# rocketradio.net
KiCad netlist of a schematic drawn in EAGLE
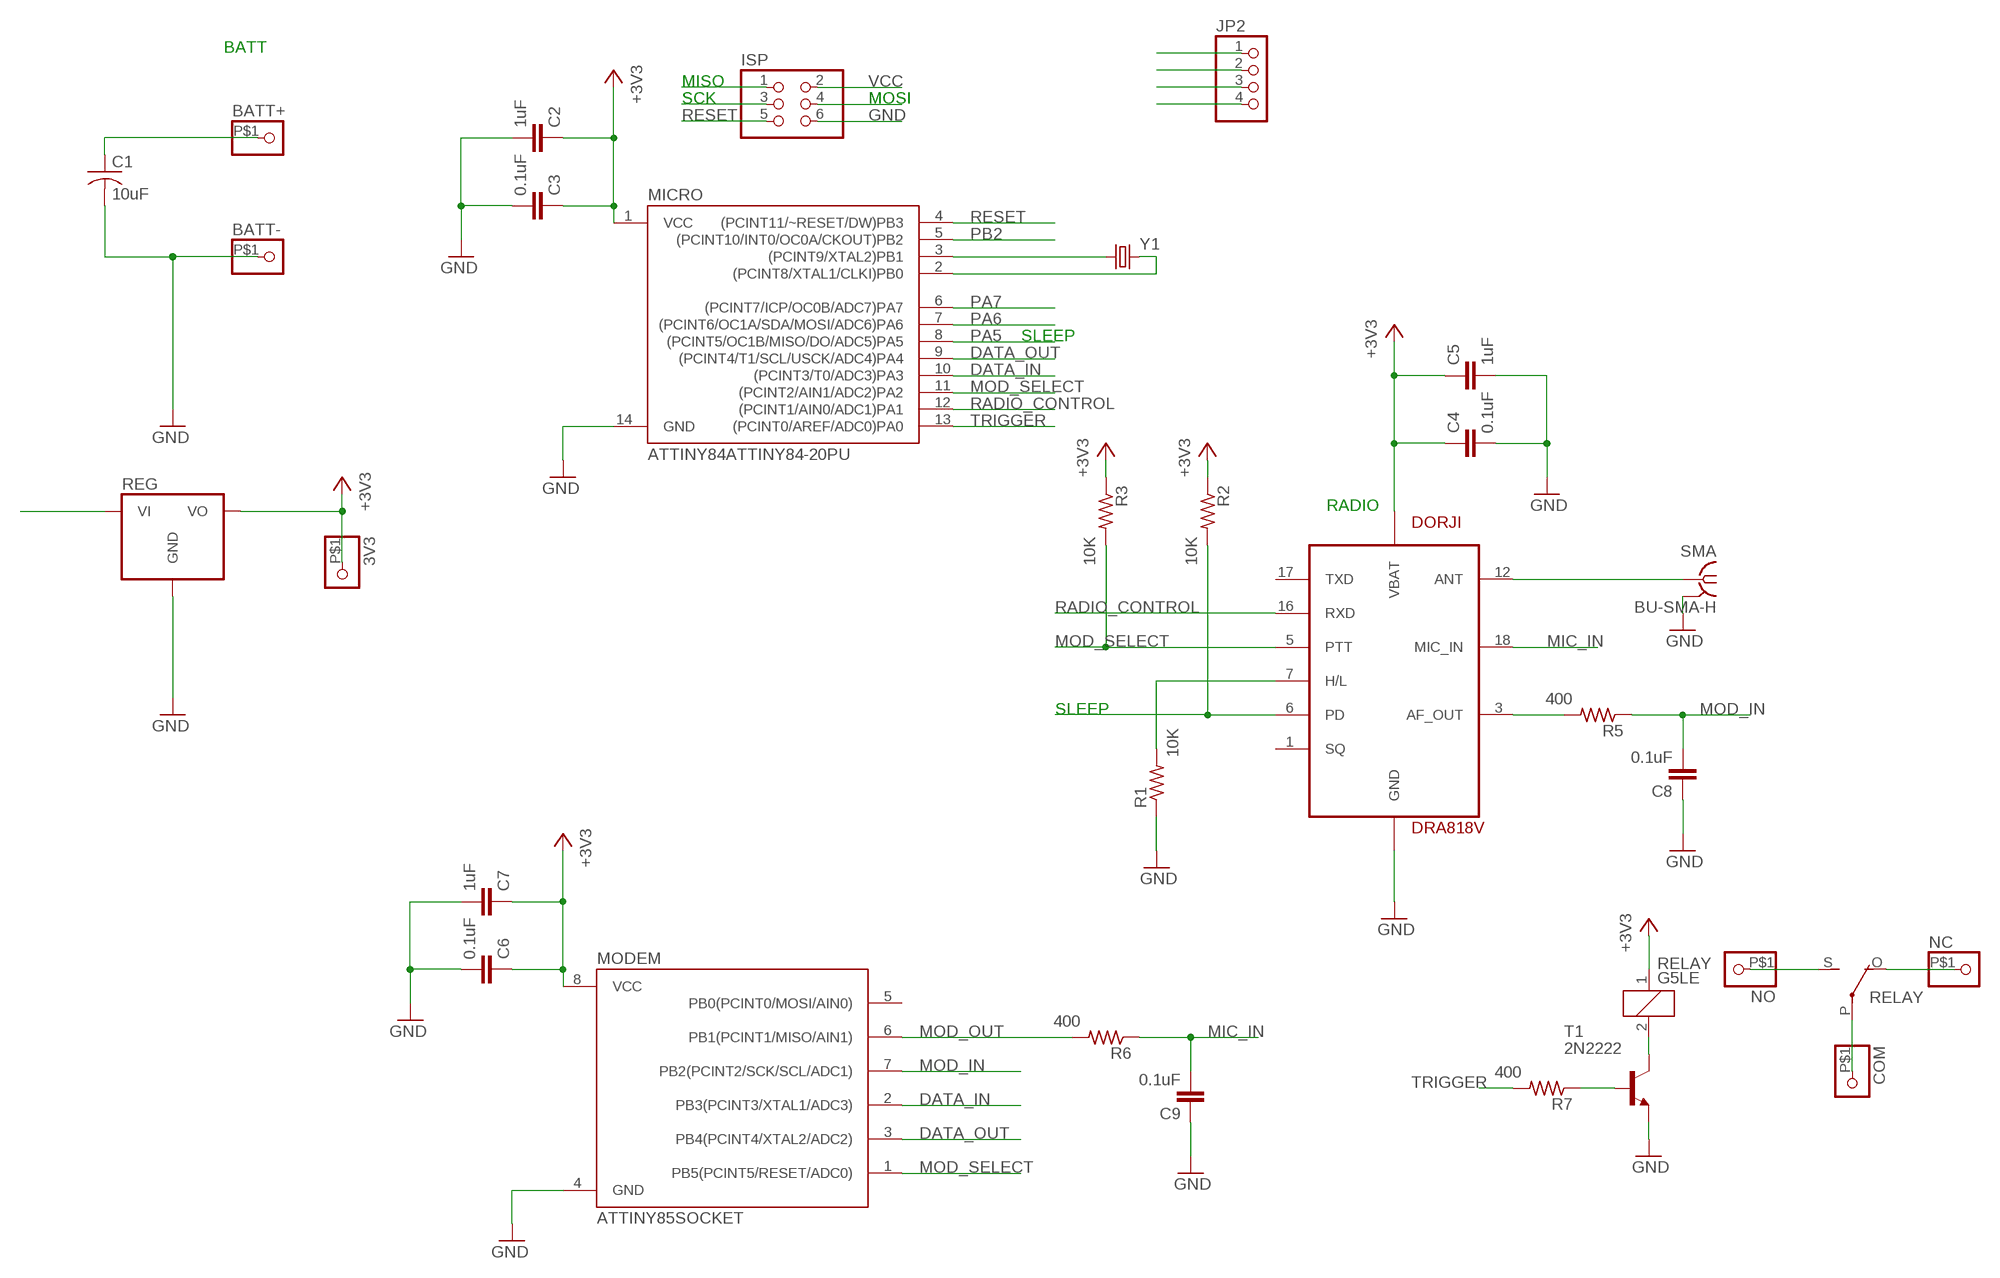
[diagram p0: schematic, sheet 1]

(export (version "E")
  (design (tool "Eeschema 10.0.6"))
  (components
    (comp (ref "3V3")
      (value "PINHD-1X1")
      (footprint "eagle-import:1X01")
      (libsource (lib "eagle-import") (part "PINHD-1X1"))
    )
    (comp (ref "BATT+")
      (value "PINHD-1X1")
      (footprint "eagle-import:1X01")
      (libsource (lib "eagle-import") (part "PINHD-1X1"))
    )
    (comp (ref "BATT-")
      (value "PINHD-1X1")
      (footprint "eagle-import:1X01")
      (libsource (lib "eagle-import") (part "PINHD-1X1"))
    )
    (comp (ref "C1")
      (value "10uF")
      (footprint "eagle-import:C025-050X050")
      (libsource (lib "eagle-import") (part "C-US025-050X050"))
    )
    (comp (ref "C2")
      (value "1uF")
      (footprint "eagle-import:C0603")
      (libsource (lib "eagle-import") (part "C-EUC0603"))
    )
    (comp (ref "C3")
      (value "0.1uF")
      (footprint "eagle-import:C0603")
      (libsource (lib "eagle-import") (part "C-EUC0603"))
    )
    (comp (ref "C4")
      (value "0.1uF")
      (footprint "eagle-import:C0603")
      (libsource (lib "eagle-import") (part "C-EUC0603"))
    )
    (comp (ref "C5")
      (value "1uF")
      (footprint "eagle-import:C0603")
      (libsource (lib "eagle-import") (part "C-EUC0603"))
    )
    (comp (ref "C6")
      (value "0.1uF")
      (footprint "eagle-import:C0603")
      (libsource (lib "eagle-import") (part "C-EUC0603"))
    )
    (comp (ref "C7")
      (value "1uF")
      (footprint "eagle-import:C0603")
      (libsource (lib "eagle-import") (part "C-EUC0603"))
    )
    (comp (ref "C8")
      (value "0.1uF")
      (footprint "eagle-import:C0603")
      (libsource (lib "eagle-import") (part "C-EUC0603"))
    )
    (comp (ref "C9")
      (value "0.1uF")
      (footprint "eagle-import:C0603")
      (libsource (lib "eagle-import") (part "C-EUC0603"))
    )
    (comp (ref "COM")
      (value "PINHD-1X1")
      (footprint "eagle-import:1X01")
      (libsource (lib "eagle-import") (part "PINHD-1X1"))
    )
    (comp (ref "DORJI")
      (value "DRA818V")
      (footprint "eagle-import:DORJI")
      (libsource (lib "eagle-import") (part "DORJIDRA818V"))
    )
    (comp (ref "ISP")
      (value "PINHD-2X3")
      (footprint "eagle-import:2X03")
      (libsource (lib "eagle-import") (part "PINHD-2X3"))
    )
    (comp (ref "JP2")
      (value "PINHD-1X4")
      (footprint "eagle-import:1X04")
      (libsource (lib "eagle-import") (part "PINHD-1X4"))
    )
    (comp (ref "MICRO")
      (value "ATTINY84ATTINY84-20PU")
      (footprint "eagle-import:DIL14")
      (libsource (lib "eagle-import") (part "ATTINY84ATTINY84-20PU"))
    )
    (comp (ref "MODEM")
      (value "ATTINY85SOCKET")
      (footprint "eagle-import:SOCKET-08")
      (libsource (lib "eagle-import") (part "ATTINY85SOCKET"))
    )
    (comp (ref "NC")
      (value "PINHD-1X1")
      (footprint "eagle-import:1X01")
      (libsource (lib "eagle-import") (part "PINHD-1X1"))
    )
    (comp (ref "NO")
      (value "PINHD-1X1")
      (footprint "eagle-import:1X01")
      (libsource (lib "eagle-import") (part "PINHD-1X1"))
    )
    (comp (ref "R1")
      (value "10K")
      (footprint "eagle-import:R0603")
      (libsource (lib "eagle-import") (part "R-US_R0603"))
    )
    (comp (ref "R2")
      (value "10K")
      (footprint "eagle-import:R0603")
      (libsource (lib "eagle-import") (part "R-US_R0603"))
    )
    (comp (ref "R3")
      (value "10K")
      (footprint "eagle-import:R0603")
      (libsource (lib "eagle-import") (part "R-US_R0603"))
    )
    (comp (ref "R5")
      (value "400")
      (footprint "eagle-import:R0603")
      (libsource (lib "eagle-import") (part "R-US_R0603"))
    )
    (comp (ref "R6")
      (value "400")
      (footprint "eagle-import:R0603")
      (libsource (lib "eagle-import") (part "R-US_R0603"))
    )
    (comp (ref "R7")
      (value "400")
      (footprint "eagle-import:R0603")
      (libsource (lib "eagle-import") (part "R-US_R0603"))
    )
    (comp (ref "REG")
      (value "AP1117-3.3SOT223")
      (footprint "eagle-import:SOT223")
      (libsource (lib "eagle-import") (part "AP1117-3.3SOT223"))
    )
    (comp (ref "RELAY")
      (value "G5LE")
      (footprint "eagle-import:G5LE")
      (libsource (lib "eagle-import") (part "G5LE"))
    )
    (comp (ref "SMA")
      (value "BU-SMA-H")
      (footprint "eagle-import:BU-SMA-H")
      (libsource (lib "eagle-import") (part "BU-SMA-H"))
    )
    (comp (ref "T1")
      (value "2N2222")
      (footprint "eagle-import:TO18")
      (libsource (lib "eagle-import") (part "2N2222"))
    )
    (comp (ref "Y1")
      (value "CRYSTAL")
      (footprint "eagle-import:MYSMD2_RESONATOR")
      (libsource (lib "eagle-import") (part "CRYSTAL"))
    )
  )
  (nets
    (net (code "1") (name "+3V3") (class "Default")
      (node (ref "3V3") (pin "P$1") (pinfunction "1_P$1") (pintype "passive"))
      (node (ref "C2") (pin "1") (pinfunction "1_1") (pintype "passive"))
      (node (ref "C3") (pin "1") (pinfunction "1_1") (pintype "passive"))
      (node (ref "C4") (pin "1") (pinfunction "1_1") (pintype "passive"))
      (node (ref "C5") (pin "1") (pinfunction "1_1") (pintype "passive"))
      (node (ref "C6") (pin "1") (pinfunction "1_1") (pintype "passive"))
      (node (ref "C7") (pin "1") (pinfunction "1_1") (pintype "passive"))
      (node (ref "DORJI") (pin "8") (pinfunction "VBAT_8") (pintype "bidirectional"))
      (node (ref "MICRO") (pin "1") (pinfunction "VCC_1") (pintype "bidirectional"))
      (node (ref "MODEM") (pin "8") (pinfunction "VCC_8") (pintype "bidirectional"))
      (node (ref "R2") (pin "1") (pinfunction "1_1") (pintype "passive"))
      (node (ref "R3") (pin "1") (pinfunction "1_1") (pintype "passive"))
      (node (ref "REG") (pin "2") (pinfunction "VO_2") (pintype "passive"))
      (node (ref "REG") (pin "4") (pinfunction "VO_4") (pintype "passive"))
      (node (ref "RELAY") (pin "1") (pinfunction "1_1") (pintype "passive"))
    )
    (net (code "2") (name "/BATT") (class "Default")
      (node (ref "BATT+") (pin "P$1") (pinfunction "1_P$1") (pintype "passive"))
      (node (ref "C1") (pin "1") (pinfunction "1_1") (pintype "passive"))
      (node (ref "REG") (pin "3") (pinfunction "VI_3") (pintype "input"))
    )
    (net (code "3") (name "/DATA_IN") (class "Default")
      (node (ref "MICRO") (pin "10") (pinfunction "(PCINT3/T0/ADC3)PA3_10") (pintype "bidirectional"))
      (node (ref "MODEM") (pin "2") (pinfunction "PB3(PCINT3/XTAL1/ADC3)_2") (pintype "bidirectional"))
    )
    (net (code "4") (name "/DATA_OUT") (class "Default")
      (node (ref "ISP") (pin "3") (pinfunction "3_3") (pintype "passive"))
      (node (ref "MICRO") (pin "9") (pinfunction "(PCINT4/T1/SCL/USCK/ADC4)PA4_9") (pintype "bidirectional"))
      (node (ref "MODEM") (pin "3") (pinfunction "PB4(PCINT4/XTAL2/ADC2)_3") (pintype "bidirectional"))
    )
    (net (code "5") (name "/MIC_IN") (class "Default")
      (node (ref "C9") (pin "2") (pinfunction "2_2") (pintype "passive"))
      (node (ref "DORJI") (pin "18") (pinfunction "MIC_IN_18") (pintype "bidirectional"))
      (node (ref "R6") (pin "1") (pinfunction "1_1") (pintype "passive"))
    )
    (net (code "6") (name "/MOD_IN") (class "Default")
      (node (ref "C8") (pin "2") (pinfunction "2_2") (pintype "passive"))
      (node (ref "MODEM") (pin "7") (pinfunction "PB2(PCINT2/SCK/SCL/ADC1)_7") (pintype "bidirectional"))
      (node (ref "R5") (pin "1") (pinfunction "1_1") (pintype "passive"))
    )
    (net (code "7") (name "/MOD_OUT") (class "Default")
      (node (ref "MODEM") (pin "6") (pinfunction "PB1(PCINT1/MISO/AIN1)_6") (pintype "bidirectional"))
      (node (ref "R6") (pin "2") (pinfunction "2_2") (pintype "passive"))
    )
    (net (code "8") (name "/MOD_SELECT") (class "Default")
      (node (ref "DORJI") (pin "5") (pinfunction "PTT_5") (pintype "bidirectional"))
      (node (ref "MICRO") (pin "11") (pinfunction "(PCINT2/AIN1/ADC2)PA2_11") (pintype "bidirectional"))
      (node (ref "MODEM") (pin "1") (pinfunction "PB5(PCINT5/RESET/ADC0)_1") (pintype "bidirectional"))
      (node (ref "R3") (pin "2") (pinfunction "2_2") (pintype "passive"))
    )
    (net (code "9") (name "/PA5") (class "Default")
      (node (ref "DORJI") (pin "6") (pinfunction "PD_6") (pintype "bidirectional"))
      (node (ref "ISP") (pin "1") (pinfunction "1_1") (pintype "passive"))
      (node (ref "JP2") (pin "4") (pinfunction "4_4") (pintype "passive"))
      (node (ref "MICRO") (pin "8") (pinfunction "(PCINT5/OC1B/MISO/DO/ADC5)PA5_8") (pintype "bidirectional"))
      (node (ref "R2") (pin "2") (pinfunction "2_2") (pintype "passive"))
    )
    (net (code "10") (name "/PA6") (class "Default")
      (node (ref "ISP") (pin "4") (pinfunction "4_4") (pintype "passive"))
      (node (ref "JP2") (pin "3") (pinfunction "3_3") (pintype "passive"))
      (node (ref "MICRO") (pin "7") (pinfunction "(PCINT6/OC1A/SDA/MOSI/ADC6)PA6_7") (pintype "bidirectional"))
    )
    (net (code "11") (name "/PA7") (class "Default")
      (node (ref "JP2") (pin "2") (pinfunction "2_2") (pintype "passive"))
      (node (ref "MICRO") (pin "6") (pinfunction "(PCINT7/ICP/OC0B/ADC7)PA7_6") (pintype "bidirectional"))
    )
    (net (code "12") (name "/PB2") (class "Default")
      (node (ref "JP2") (pin "1") (pinfunction "1_1") (pintype "passive"))
      (node (ref "MICRO") (pin "5") (pinfunction "(PCINT10/INT0/OC0A/CKOUT)PB2_5") (pintype "bidirectional"))
    )
    (net (code "13") (name "/RADIO_CONTROL") (class "Default")
      (node (ref "DORJI") (pin "16") (pinfunction "RXD_16") (pintype "bidirectional"))
      (node (ref "MICRO") (pin "12") (pinfunction "(PCINT1/AIN0/ADC1)PA1_12") (pintype "bidirectional"))
    )
    (net (code "14") (name "/RESET") (class "Default")
      (node (ref "ISP") (pin "5") (pinfunction "5_5") (pintype "passive"))
      (node (ref "MICRO") (pin "4") (pinfunction "(PCINT11/~{RESET/DW})PB3_4") (pintype "bidirectional"))
    )
    (net (code "15") (name "/TRIGGER") (class "Default")
      (node (ref "MICRO") (pin "13") (pinfunction "(PCINT0/AREF/ADC0)PA0_13") (pintype "bidirectional"))
      (node (ref "R7") (pin "2") (pinfunction "2_2") (pintype "passive"))
    )
    (net (code "16") (name "/VCC") (class "Default")
      (node (ref "ISP") (pin "2") (pinfunction "2_2") (pintype "passive"))
    )
    (net (code "17") (name "GND") (class "Default")
      (node (ref "BATT-") (pin "P$1") (pinfunction "1_P$1") (pintype "passive"))
      (node (ref "C1") (pin "2") (pinfunction "2_2") (pintype "passive"))
      (node (ref "C2") (pin "2") (pinfunction "2_2") (pintype "passive"))
      (node (ref "C3") (pin "2") (pinfunction "2_2") (pintype "passive"))
      (node (ref "C4") (pin "2") (pinfunction "2_2") (pintype "passive"))
      (node (ref "C5") (pin "2") (pinfunction "2_2") (pintype "passive"))
      (node (ref "C6") (pin "2") (pinfunction "2_2") (pintype "passive"))
      (node (ref "C7") (pin "2") (pinfunction "2_2") (pintype "passive"))
      (node (ref "C8") (pin "1") (pinfunction "1_1") (pintype "passive"))
      (node (ref "C9") (pin "1") (pinfunction "1_1") (pintype "passive"))
      (node (ref "DORJI") (pin "10") (pinfunction "GND_10") (pintype "bidirectional"))
      (node (ref "DORJI") (pin "9") (pinfunction "GND_9") (pintype "bidirectional"))
      (node (ref "ISP") (pin "6") (pinfunction "6_6") (pintype "passive"))
      (node (ref "MICRO") (pin "14") (pinfunction "GND_14") (pintype "bidirectional"))
      (node (ref "MODEM") (pin "4") (pinfunction "GND_4") (pintype "bidirectional"))
      (node (ref "R1") (pin "1") (pinfunction "1_1") (pintype "passive"))
      (node (ref "REG") (pin "1") (pinfunction "GND_1") (pintype "input"))
      (node (ref "SMA") (pin "2") (pinfunction "2_2") (pintype "passive"))
      (node (ref "SMA") (pin "3") (pinfunction "2_3") (pintype "passive"))
      (node (ref "SMA") (pin "4") (pinfunction "2_4") (pintype "passive"))
      (node (ref "SMA") (pin "5") (pinfunction "2_5") (pintype "passive"))
      (node (ref "T1") (pin "1") (pinfunction "E_1") (pintype "passive"))
    )
    (net (code "18") (name "Net-(COM-1)") (class "Default")
      (node (ref "COM") (pin "P$1") (pinfunction "1_P$1") (pintype "passive"))
      (node (ref "RELAY") (pin "P") (pinfunction "P_P") (pintype "passive"))
    )
    (net (code "19") (name "Net-(DORJI-AF_OUT)") (class "Default")
      (node (ref "DORJI") (pin "3") (pinfunction "AF_OUT_3") (pintype "bidirectional"))
      (node (ref "R5") (pin "2") (pinfunction "2_2") (pintype "passive"))
    )
    (net (code "20") (name "Net-(DORJI-ANT)") (class "Default")
      (node (ref "DORJI") (pin "12") (pinfunction "ANT_12") (pintype "bidirectional"))
      (node (ref "SMA") (pin "1") (pinfunction "1_1") (pintype "passive"))
    )
    (net (code "21") (name "Net-(DORJI-H{slash}L)") (class "Default")
      (node (ref "DORJI") (pin "7") (pinfunction "H/L_7") (pintype "bidirectional"))
      (node (ref "R1") (pin "2") (pinfunction "2_2") (pintype "passive"))
    )
    (net (code "22") (name "Net-(MICRO-(PCINT8{slash}XTAL1{slash}CLKI)PB0)") (class "Default")
      (node (ref "MICRO") (pin "2") (pinfunction "(PCINT8/XTAL1/CLKI)PB0_2") (pintype "bidirectional"))
      (node (ref "Y1") (pin "3") (pinfunction "2_3") (pintype "passive"))
    )
    (net (code "23") (name "Net-(MICRO-(PCINT9{slash}XTAL2)PB1)") (class "Default")
      (node (ref "MICRO") (pin "3") (pinfunction "(PCINT9/XTAL2)PB1_3") (pintype "bidirectional"))
      (node (ref "Y1") (pin "1") (pinfunction "1_1") (pintype "passive"))
    )
    (net (code "24") (name "Net-(NC-1)") (class "Default")
      (node (ref "NC") (pin "P$1") (pinfunction "1_P$1") (pintype "passive"))
      (node (ref "RELAY") (pin "O") (pinfunction "O_O") (pintype "passive"))
    )
    (net (code "25") (name "Net-(NO-1)") (class "Default")
      (node (ref "NO") (pin "P$1") (pinfunction "1_P$1") (pintype "passive"))
      (node (ref "RELAY") (pin "S") (pinfunction "S_S") (pintype "passive"))
    )
    (net (code "26") (name "Net-(T1-B)") (class "Default")
      (node (ref "R7") (pin "1") (pinfunction "1_1") (pintype "passive"))
      (node (ref "T1") (pin "2") (pinfunction "B_2") (pintype "passive"))
    )
    (net (code "27") (name "Net-(T1-C)") (class "Default")
      (node (ref "RELAY") (pin "2") (pinfunction "2_2") (pintype "passive"))
      (node (ref "T1") (pin "3") (pinfunction "C_3") (pintype "passive"))
    )
    (net (code "28") (name "unconnected-(DORJI-SQ-Pad1)") (class "Default")
      (node (ref "DORJI") (pin "1") (pinfunction "SQ_1") (pintype "bidirectional"))
    )
    (net (code "29") (name "unconnected-(DORJI-TXD-Pad17)") (class "Default")
      (node (ref "DORJI") (pin "17") (pinfunction "TXD_17") (pintype "bidirectional"))
    )
    (net (code "30") (name "unconnected-(MODEM-PB0(PCINT0{slash}MOSI{slash}AIN0)-Pad5)") (class "Default")
      (node (ref "MODEM") (pin "5") (pinfunction "PB0(PCINT0/MOSI/AIN0)_5") (pintype "bidirectional"))
    )
  )
)
